# rbbb.net
KiCad netlist of a schematic drawn in EAGLE
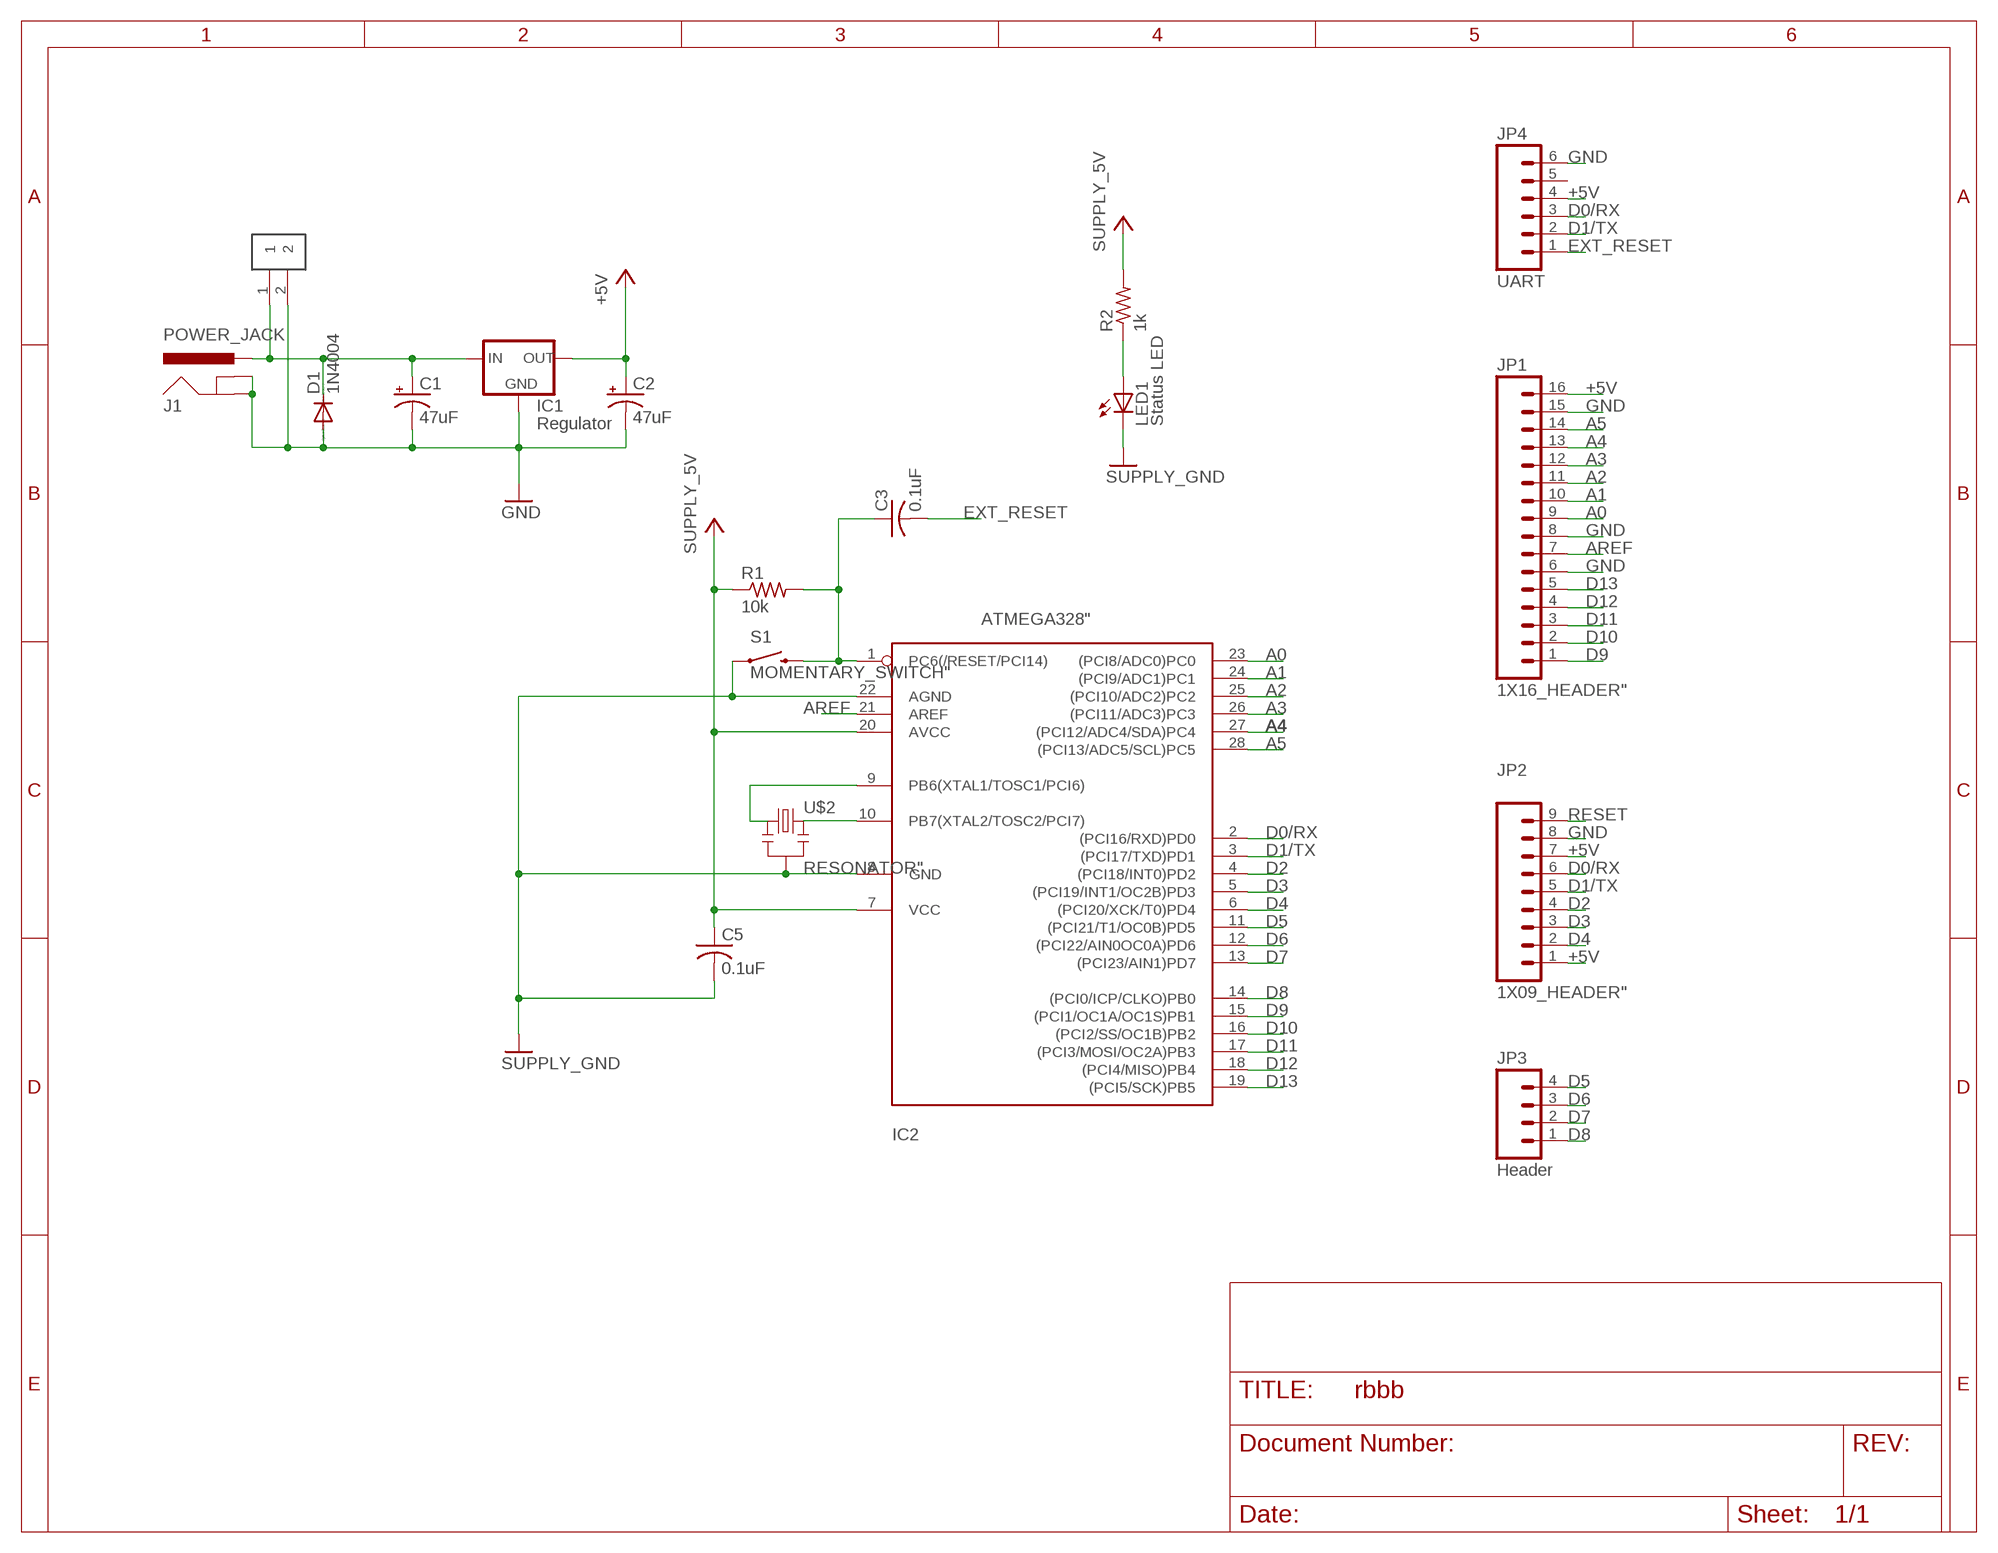
[diagram p0: schematic, sheet 1]

(export (version "E")
  (design (tool "Eeschema 10.0.6"))
  (components
    (comp (ref "C1")
      (value "47uF")
      (footprint "eagle-import:ELECTROLYTIC_CAP")
      (libsource (lib "eagle-import") (part "ELECTROLYTIC_CAP2.54MM"))
    )
    (comp (ref "C2")
      (value "47uF")
      (footprint "eagle-import:ELECTROLYTIC_CAP")
      (libsource (lib "eagle-import") (part "ELECTROLYTIC_CAP2.54MM"))
    )
    (comp (ref "C3")
      (value "0.1uF")
      (footprint "eagle-import:UNPOLARIZED_CAP")
      (libsource (lib "eagle-import") (part "UNPOLARIZED_CAP{dblquote}"))
    )
    (comp (ref "C5")
      (value "0.1uF")
      (footprint "eagle-import:UNPOLARIZED_CAP")
      (libsource (lib "eagle-import") (part "UNPOLARIZED_CAP{dblquote}"))
    )
    (comp (ref "D1")
      (value "1N4004")
      (footprint "eagle-import:DO41-10")
      (libsource (lib "eagle-import") (part "1N4004"))
    )
    (comp (ref "IC1")
      (value "Regulator")
      (footprint "eagle-import:L4931_REGULATOR")
      (libsource (lib "eagle-import") (part "REGULATOR"))
    )
    (comp (ref "IC2")
      (value "ATMEGA328\"")
      (footprint "eagle-import:ATMEGA328")
      (libsource (lib "eagle-import") (part "ATMEGA328{dblquote}"))
    )
    (comp (ref "J1")
      (value "POWER_JACK")
      (footprint "eagle-import:POWER_JACK")
      (libsource (lib "eagle-import") (part "POWER_JACK{dblquote}"))
    )
    (comp (ref "JP1")
      (value "1X16_HEADER\"")
      (footprint "eagle-import:1X16_HEADER")
      (libsource (lib "eagle-import") (part "1X16_HEADER{dblquote}"))
    )
    (comp (ref "JP2")
      (value "1X09_HEADER\"")
      (footprint "eagle-import:1X09_HEADER")
      (libsource (lib "eagle-import") (part "1X09_HEADER{dblquote}"))
    )
    (comp (ref "JP3")
      (value "Header")
      (footprint "eagle-import:1X04_HEADER")
      (libsource (lib "eagle-import") (part "1X04_HEADER{dblquote}"))
    )
    (comp (ref "JP4")
      (value "UART")
      (footprint "eagle-import:1X06_HEADER")
      (libsource (lib "eagle-import") (part "1X06_HEADER{dblquote}"))
    )
    (comp (ref "LED1")
      (value "Status LED")
      (footprint "eagle-import:LED")
      (libsource (lib "eagle-import") (part "LED3MM"))
    )
    (comp (ref "R1")
      (value "10k")
      (footprint "eagle-import:RESISTOR")
      (libsource (lib "eagle-import") (part "RESISTOR1/6WATT"))
    )
    (comp (ref "R2")
      (value "1k")
      (footprint "eagle-import:RESISTOR")
      (libsource (lib "eagle-import") (part "RESISTOR1/6WATT"))
    )
    (comp (ref "S1")
      (value "MOMENTARY_SWITCH\"")
      (footprint "eagle-import:MOMENTARY_SWITCH")
      (libsource (lib "eagle-import") (part "MOMENTARY_SWITCH{dblquote}"))
    )
    (comp (ref "U$1")
      (value "1X02_HEADER")
      (footprint "eagle-import:1X02_HEADER")
      (libsource (lib "eagle-import") (part "1X02_HEADER"))
    )
    (comp (ref "U$2")
      (value "RESONATOR\"")
      (footprint "eagle-import:RESONATOR")
      (libsource (lib "eagle-import") (part "RESONATOR{dblquote}"))
    )
  )
  (nets
    (net (code "1") (name "+5V") (class "Default")
      (node (ref "C2") (pin "+") (pinfunction "+_+") (pintype "passive"))
      (node (ref "C5") (pin "1") (pinfunction "1_1") (pintype "passive"))
      (node (ref "IC1") (pin "OUT") (pinfunction "OUT_OUT") (pintype "passive"))
      (node (ref "IC2") (pin "20") (pinfunction "AVCC_20") (pintype "bidirectional"))
      (node (ref "IC2") (pin "7") (pinfunction "VCC_7") (pintype "bidirectional"))
      (node (ref "JP1") (pin "16") (pinfunction "16_16") (pintype "passive"))
      (node (ref "JP2") (pin "1") (pinfunction "1_1") (pintype "passive"))
      (node (ref "JP2") (pin "7") (pinfunction "7_7") (pintype "passive"))
      (node (ref "JP4") (pin "4") (pinfunction "4_4") (pintype "passive"))
      (node (ref "R1") (pin "1") (pinfunction "1_1") (pintype "passive"))
      (node (ref "R2") (pin "2") (pinfunction "2_2") (pintype "passive"))
    )
    (net (code "2") (name "/A0") (class "Default")
      (node (ref "IC2") (pin "23") (pinfunction "(PCI8/ADC0)PC0_23") (pintype "bidirectional"))
      (node (ref "JP1") (pin "9") (pinfunction "9_9") (pintype "passive"))
    )
    (net (code "3") (name "/A1") (class "Default")
      (node (ref "IC2") (pin "24") (pinfunction "(PCI9/ADC1)PC1_24") (pintype "bidirectional"))
      (node (ref "JP1") (pin "10") (pinfunction "10_10") (pintype "passive"))
    )
    (net (code "4") (name "/A2") (class "Default")
      (node (ref "IC2") (pin "25") (pinfunction "(PCI10/ADC2)PC2_25") (pintype "bidirectional"))
      (node (ref "JP1") (pin "11") (pinfunction "11_11") (pintype "passive"))
    )
    (net (code "5") (name "/A3") (class "Default")
      (node (ref "IC2") (pin "26") (pinfunction "(PCI11/ADC3)PC3_26") (pintype "bidirectional"))
      (node (ref "JP1") (pin "12") (pinfunction "12_12") (pintype "passive"))
    )
    (net (code "6") (name "/A4") (class "Default")
      (node (ref "IC2") (pin "27") (pinfunction "(PCI12/ADC4/SDA)PC4_27") (pintype "bidirectional"))
      (node (ref "JP1") (pin "13") (pinfunction "13_13") (pintype "passive"))
    )
    (net (code "7") (name "/A5") (class "Default")
      (node (ref "IC2") (pin "28") (pinfunction "(PCI13/ADC5/SCL)PC5_28") (pintype "bidirectional"))
      (node (ref "JP1") (pin "14") (pinfunction "14_14") (pintype "passive"))
    )
    (net (code "8") (name "/AREF") (class "Default")
      (node (ref "IC2") (pin "21") (pinfunction "AREF_21") (pintype "bidirectional"))
      (node (ref "JP1") (pin "7") (pinfunction "7_7") (pintype "passive"))
    )
    (net (code "9") (name "/D0{slash}RX") (class "Default")
      (node (ref "IC2") (pin "2") (pinfunction "(PCI16/RXD)PD0_2") (pintype "bidirectional"))
      (node (ref "JP2") (pin "6") (pinfunction "6_6") (pintype "passive"))
      (node (ref "JP4") (pin "3") (pinfunction "3_3") (pintype "passive"))
    )
    (net (code "10") (name "/D1{slash}TX") (class "Default")
      (node (ref "IC2") (pin "3") (pinfunction "(PCI17/TXD)PD1_3") (pintype "bidirectional"))
      (node (ref "JP2") (pin "5") (pinfunction "5_5") (pintype "passive"))
      (node (ref "JP4") (pin "2") (pinfunction "2_2") (pintype "passive"))
    )
    (net (code "11") (name "/D2") (class "Default")
      (node (ref "IC2") (pin "4") (pinfunction "(PCI18/INT0)PD2_4") (pintype "bidirectional"))
      (node (ref "JP2") (pin "4") (pinfunction "4_4") (pintype "passive"))
    )
    (net (code "12") (name "/D3") (class "Default")
      (node (ref "IC2") (pin "5") (pinfunction "(PCI19/INT1/OC2B)PD3_5") (pintype "bidirectional"))
      (node (ref "JP2") (pin "3") (pinfunction "3_3") (pintype "passive"))
    )
    (net (code "13") (name "/D4") (class "Default")
      (node (ref "IC2") (pin "6") (pinfunction "(PCI20/XCK/T0)PD4_6") (pintype "bidirectional"))
      (node (ref "JP2") (pin "2") (pinfunction "2_2") (pintype "passive"))
    )
    (net (code "14") (name "/D5") (class "Default")
      (node (ref "IC2") (pin "11") (pinfunction "(PCI21/T1/OC0B)PD5_11") (pintype "bidirectional"))
      (node (ref "JP3") (pin "4") (pinfunction "4_4") (pintype "passive"))
    )
    (net (code "15") (name "/D6") (class "Default")
      (node (ref "IC2") (pin "12") (pinfunction "(PCI22/AIN0OC0A)PD6_12") (pintype "bidirectional"))
      (node (ref "JP3") (pin "3") (pinfunction "3_3") (pintype "passive"))
    )
    (net (code "16") (name "/D7") (class "Default")
      (node (ref "IC2") (pin "13") (pinfunction "(PCI23/AIN1)PD7_13") (pintype "bidirectional"))
      (node (ref "JP3") (pin "2") (pinfunction "2_2") (pintype "passive"))
    )
    (net (code "17") (name "/D8") (class "Default")
      (node (ref "IC2") (pin "14") (pinfunction "(PCI0/ICP/CLKO)PB0_14") (pintype "bidirectional"))
      (node (ref "JP3") (pin "1") (pinfunction "1_1") (pintype "passive"))
    )
    (net (code "18") (name "/D9") (class "Default")
      (node (ref "IC2") (pin "15") (pinfunction "(PCI1/OC1A/OC1S)PB1_15") (pintype "bidirectional"))
      (node (ref "JP1") (pin "1") (pinfunction "1_1") (pintype "passive"))
    )
    (net (code "19") (name "/D10") (class "Default")
      (node (ref "IC2") (pin "16") (pinfunction "(PCI2/SS/OC1B)PB2_16") (pintype "bidirectional"))
      (node (ref "JP1") (pin "2") (pinfunction "2_2") (pintype "passive"))
    )
    (net (code "20") (name "/D11") (class "Default")
      (node (ref "IC2") (pin "17") (pinfunction "(PCI3/MOSI/OC2A)PB3_17") (pintype "bidirectional"))
      (node (ref "JP1") (pin "3") (pinfunction "3_3") (pintype "passive"))
    )
    (net (code "21") (name "/D12") (class "Default")
      (node (ref "IC2") (pin "18") (pinfunction "(PCI4/MISO)PB4_18") (pintype "bidirectional"))
      (node (ref "JP1") (pin "4") (pinfunction "4_4") (pintype "passive"))
    )
    (net (code "22") (name "/D13") (class "Default")
      (node (ref "IC2") (pin "19") (pinfunction "(PCI5/SCK)PB5_19") (pintype "bidirectional"))
      (node (ref "JP1") (pin "5") (pinfunction "5_5") (pintype "passive"))
    )
    (net (code "23") (name "/EXT_RESET") (class "Default")
      (node (ref "C3") (pin "2") (pinfunction "2_2") (pintype "passive"))
      (node (ref "JP4") (pin "1") (pinfunction "1_1") (pintype "passive"))
    )
    (net (code "24") (name "/RESET") (class "Default")
      (node (ref "JP2") (pin "9") (pinfunction "9_9") (pintype "passive"))
    )
    (net (code "25") (name "GND") (class "Default")
      (node (ref "C1") (pin "-") (pinfunction "-_-") (pintype "passive"))
      (node (ref "C2") (pin "-") (pinfunction "-_-") (pintype "passive"))
      (node (ref "C5") (pin "2") (pinfunction "2_2") (pintype "passive"))
      (node (ref "D1") (pin "A") (pinfunction "A_A") (pintype "passive"))
      (node (ref "IC1") (pin "GND") (pinfunction "GND_GND") (pintype "input"))
      (node (ref "IC2") (pin "22") (pinfunction "AGND_22") (pintype "bidirectional"))
      (node (ref "IC2") (pin "8") (pinfunction "GND_8") (pintype "bidirectional"))
      (node (ref "J1") (pin "GND") (pinfunction "GND_GND") (pintype "bidirectional"))
      (node (ref "J1") (pin "GNDBREAK") (pinfunction "GNDBREAK_GNDBREAK") (pintype "bidirectional"))
      (node (ref "JP1") (pin "15") (pinfunction "15_15") (pintype "passive"))
      (node (ref "JP1") (pin "6") (pinfunction "6_6") (pintype "passive"))
      (node (ref "JP1") (pin "8") (pinfunction "8_8") (pintype "passive"))
      (node (ref "JP2") (pin "8") (pinfunction "8_8") (pintype "passive"))
      (node (ref "JP4") (pin "6") (pinfunction "6_6") (pintype "passive"))
      (node (ref "LED1") (pin "K") (pinfunction "C_K") (pintype "passive"))
      (node (ref "S1") (pin "1") (pinfunction "1_1") (pintype "passive"))
      (node (ref "U$1") (pin "2") (pinfunction "2_2") (pintype "bidirectional"))
      (node (ref "U$2") (pin "2") (pinfunction "2_2") (pintype "passive"))
    )
    (net (code "26") (name "Net-(C1-Pad+)") (class "Default")
      (node (ref "C1") (pin "+") (pinfunction "+_+") (pintype "passive"))
      (node (ref "D1") (pin "C") (pinfunction "C_C") (pintype "passive"))
      (node (ref "IC1") (pin "IN") (pinfunction "IN_IN") (pintype "input"))
      (node (ref "J1") (pin "PWR") (pinfunction "PWR_PWR") (pintype "bidirectional"))
      (node (ref "U$1") (pin "1") (pinfunction "1_1") (pintype "bidirectional"))
    )
    (net (code "27") (name "Net-(IC2-PB6(XTAL1{slash}TOSC1{slash}PCI6))") (class "Default")
      (node (ref "IC2") (pin "9") (pinfunction "PB6(XTAL1/TOSC1/PCI6)_9") (pintype "bidirectional"))
      (node (ref "U$2") (pin "1") (pinfunction "1_1") (pintype "passive"))
    )
    (net (code "28") (name "Net-(IC2-PB7(XTAL2{slash}TOSC2{slash}PCI7))") (class "Default")
      (node (ref "IC2") (pin "10") (pinfunction "PB7(XTAL2/TOSC2/PCI7)_10") (pintype "bidirectional"))
      (node (ref "U$2") (pin "3") (pinfunction "3_3") (pintype "passive"))
    )
    (net (code "29") (name "Net-(IC2-PC6({slash}RESET{slash}PCI14))") (class "Default")
      (node (ref "C3") (pin "1") (pinfunction "1_1") (pintype "passive"))
      (node (ref "IC2") (pin "1") (pinfunction "PC6(/RESET/PCI14)_1") (pintype "bidirectional"))
      (node (ref "R1") (pin "2") (pinfunction "2_2") (pintype "passive"))
      (node (ref "S1") (pin "3") (pinfunction "2_3") (pintype "passive"))
    )
    (net (code "30") (name "Net-(LED1-PadA)") (class "Default")
      (node (ref "LED1") (pin "A") (pinfunction "A_A") (pintype "passive"))
      (node (ref "R2") (pin "1") (pinfunction "1_1") (pintype "passive"))
    )
    (net (code "31") (name "unconnected-(JP4-Pad5)") (class "Default")
      (node (ref "JP4") (pin "5") (pinfunction "5_5") (pintype "passive"))
    )
  )
)
